# hub.net
KiCad netlist of a schematic drawn in EAGLE
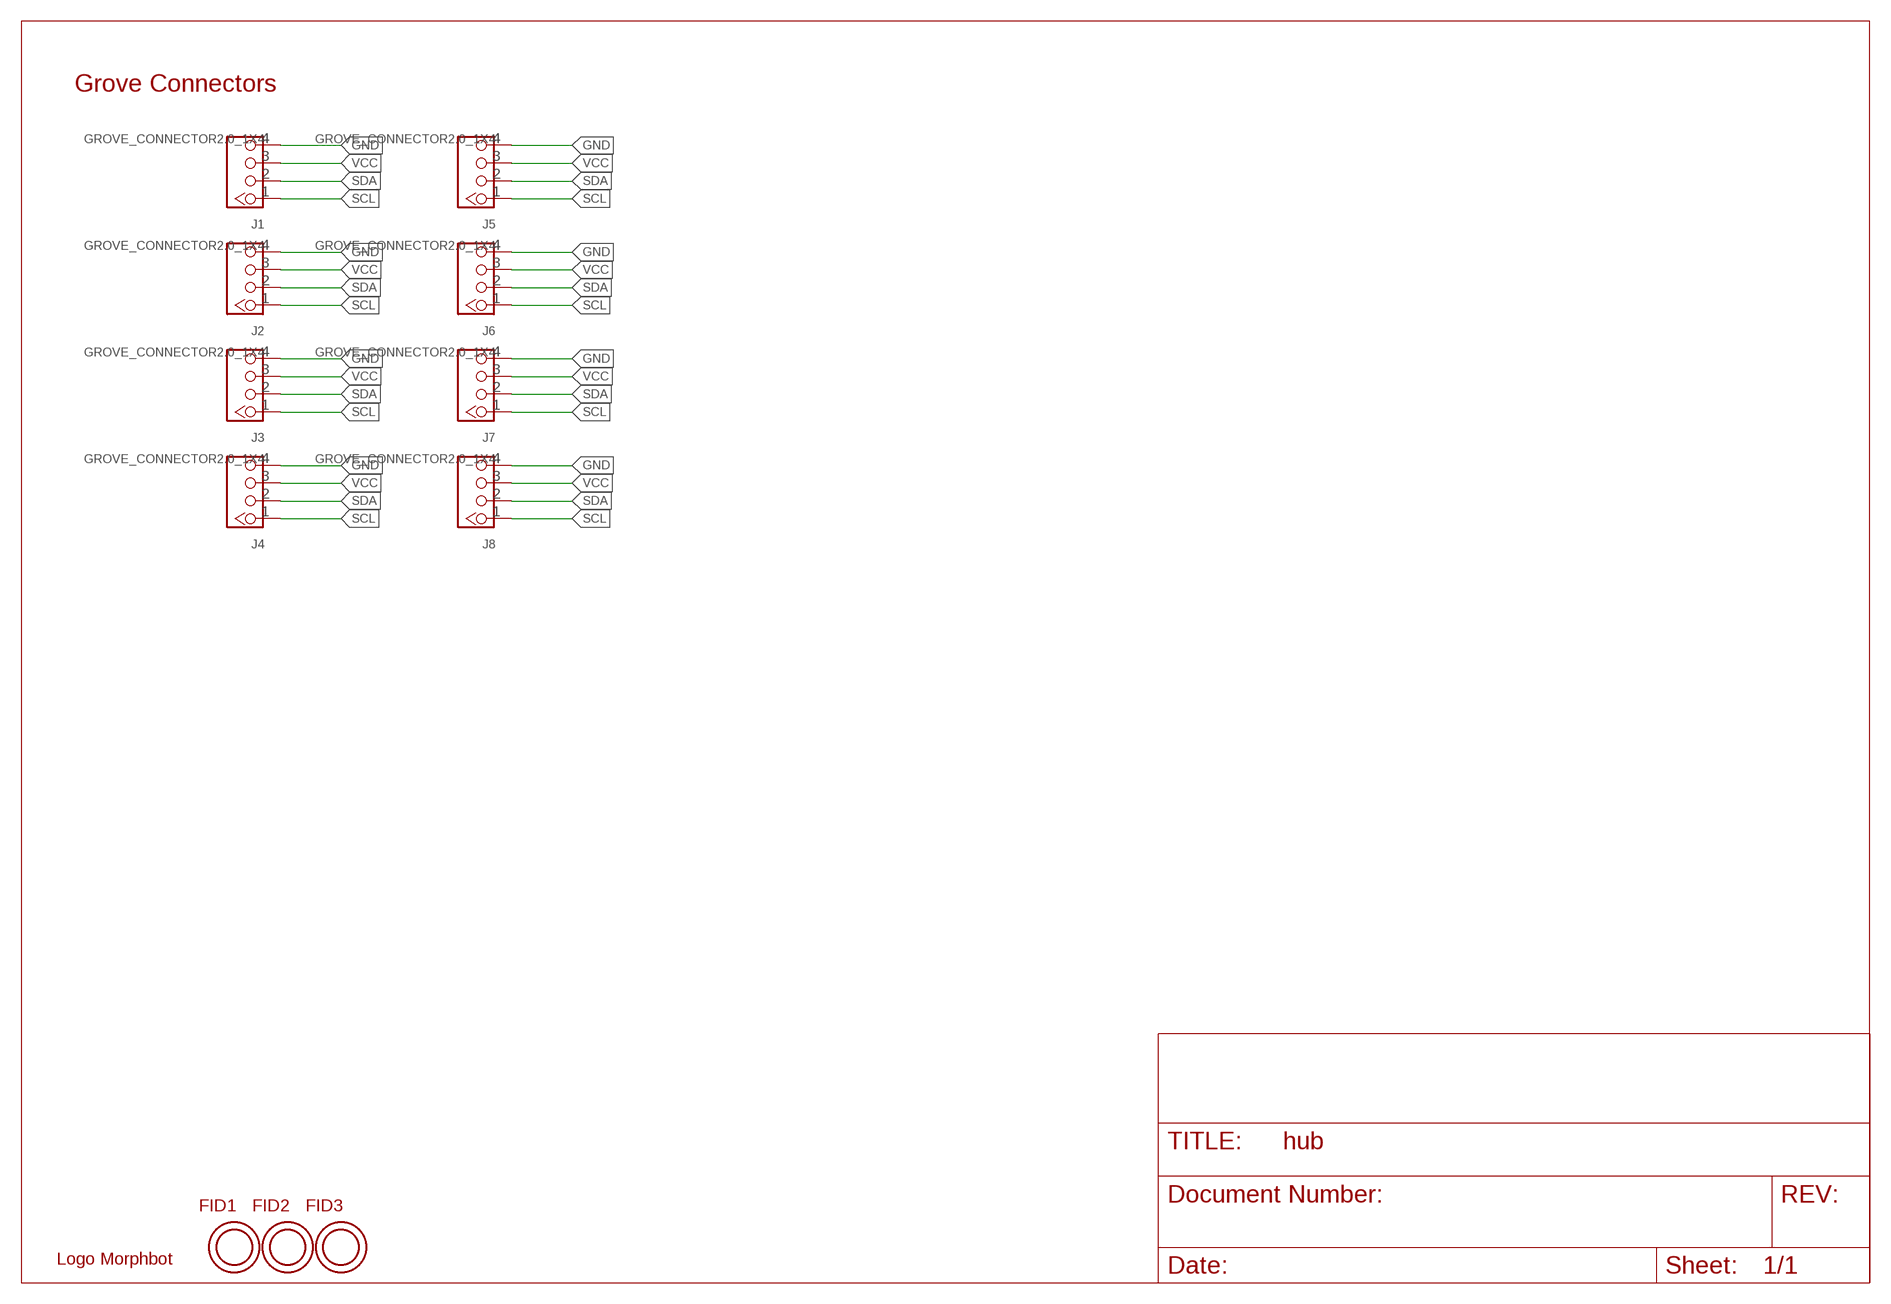
[diagram p0: schematic, sheet 1]

(export (version "E")
  (design (tool "Eeschema 10.0.6"))
  (components
    (comp (ref "FID1")
      (value "OPEN-PNP-FIDUCIAL")
      (footprint "eagle-import:OPEN-PNP-FIDUCIAL")
      (libsource (lib "eagle-import") (part "OPEN-PNP-FIDUCIAL"))
    )
    (comp (ref "FID2")
      (value "OPEN-PNP-FIDUCIAL")
      (footprint "eagle-import:OPEN-PNP-FIDUCIAL")
      (libsource (lib "eagle-import") (part "OPEN-PNP-FIDUCIAL"))
    )
    (comp (ref "FID3")
      (value "OPEN-PNP-FIDUCIAL")
      (footprint "eagle-import:OPEN-PNP-FIDUCIAL")
      (libsource (lib "eagle-import") (part "OPEN-PNP-FIDUCIAL"))
    )
    (comp (ref "J1")
      (value "GROVE_CONNECTOR2.0_1X4")
      (footprint "eagle-import:2.0_1X4_STRAIGHT")
      (libsource (lib "eagle-import") (part "GROVE_CONNECTOR2.0_1X4"))
    )
    (comp (ref "J2")
      (value "GROVE_CONNECTOR2.0_1X4")
      (footprint "eagle-import:2.0_1X4_STRAIGHT")
      (libsource (lib "eagle-import") (part "GROVE_CONNECTOR2.0_1X4"))
    )
    (comp (ref "J3")
      (value "GROVE_CONNECTOR2.0_1X4")
      (footprint "eagle-import:2.0_1X4_STRAIGHT")
      (libsource (lib "eagle-import") (part "GROVE_CONNECTOR2.0_1X4"))
    )
    (comp (ref "J4")
      (value "GROVE_CONNECTOR2.0_1X4")
      (footprint "eagle-import:2.0_1X4_STRAIGHT")
      (libsource (lib "eagle-import") (part "GROVE_CONNECTOR2.0_1X4"))
    )
    (comp (ref "J5")
      (value "GROVE_CONNECTOR2.0_1X4")
      (footprint "eagle-import:2.0_1X4_STRAIGHT")
      (libsource (lib "eagle-import") (part "GROVE_CONNECTOR2.0_1X4"))
    )
    (comp (ref "J6")
      (value "GROVE_CONNECTOR2.0_1X4")
      (footprint "eagle-import:2.0_1X4_STRAIGHT")
      (libsource (lib "eagle-import") (part "GROVE_CONNECTOR2.0_1X4"))
    )
    (comp (ref "J7")
      (value "GROVE_CONNECTOR2.0_1X4")
      (footprint "eagle-import:2.0_1X4_STRAIGHT")
      (libsource (lib "eagle-import") (part "GROVE_CONNECTOR2.0_1X4"))
    )
    (comp (ref "J8")
      (value "GROVE_CONNECTOR2.0_1X4")
      (footprint "eagle-import:2.0_1X4_STRAIGHT")
      (libsource (lib "eagle-import") (part "GROVE_CONNECTOR2.0_1X4"))
    )
    (comp (ref "U$1")
      (value "LOGO_MORPHBOT5MM")
      (footprint "eagle-import:LOGO_MORPHBOT")
      (libsource (lib "eagle-import") (part "LOGO_MORPHBOT5MM"))
    )
  )
  (nets
    (net (code "1") (name "GND") (class "Default")
      (node (ref "J1") (pin "4") (pinfunction "4_4") (pintype "bidirectional"))
      (node (ref "J2") (pin "4") (pinfunction "4_4") (pintype "bidirectional"))
      (node (ref "J3") (pin "4") (pinfunction "4_4") (pintype "bidirectional"))
      (node (ref "J4") (pin "4") (pinfunction "4_4") (pintype "bidirectional"))
      (node (ref "J5") (pin "4") (pinfunction "4_4") (pintype "bidirectional"))
      (node (ref "J6") (pin "4") (pinfunction "4_4") (pintype "bidirectional"))
      (node (ref "J7") (pin "4") (pinfunction "4_4") (pintype "bidirectional"))
      (node (ref "J8") (pin "4") (pinfunction "4_4") (pintype "bidirectional"))
    )
    (net (code "2") (name "SCL") (class "Default")
      (node (ref "J1") (pin "1") (pinfunction "1_1") (pintype "bidirectional"))
      (node (ref "J2") (pin "1") (pinfunction "1_1") (pintype "bidirectional"))
      (node (ref "J3") (pin "1") (pinfunction "1_1") (pintype "bidirectional"))
      (node (ref "J4") (pin "1") (pinfunction "1_1") (pintype "bidirectional"))
      (node (ref "J5") (pin "1") (pinfunction "1_1") (pintype "bidirectional"))
      (node (ref "J6") (pin "1") (pinfunction "1_1") (pintype "bidirectional"))
      (node (ref "J7") (pin "1") (pinfunction "1_1") (pintype "bidirectional"))
      (node (ref "J8") (pin "1") (pinfunction "1_1") (pintype "bidirectional"))
    )
    (net (code "3") (name "SDA") (class "Default")
      (node (ref "J1") (pin "2") (pinfunction "2_2") (pintype "bidirectional"))
      (node (ref "J2") (pin "2") (pinfunction "2_2") (pintype "bidirectional"))
      (node (ref "J3") (pin "2") (pinfunction "2_2") (pintype "bidirectional"))
      (node (ref "J4") (pin "2") (pinfunction "2_2") (pintype "bidirectional"))
      (node (ref "J5") (pin "2") (pinfunction "2_2") (pintype "bidirectional"))
      (node (ref "J6") (pin "2") (pinfunction "2_2") (pintype "bidirectional"))
      (node (ref "J7") (pin "2") (pinfunction "2_2") (pintype "bidirectional"))
      (node (ref "J8") (pin "2") (pinfunction "2_2") (pintype "bidirectional"))
    )
    (net (code "4") (name "VCC") (class "Default")
      (node (ref "J1") (pin "3") (pinfunction "3_3") (pintype "bidirectional"))
      (node (ref "J2") (pin "3") (pinfunction "3_3") (pintype "bidirectional"))
      (node (ref "J3") (pin "3") (pinfunction "3_3") (pintype "bidirectional"))
      (node (ref "J4") (pin "3") (pinfunction "3_3") (pintype "bidirectional"))
      (node (ref "J5") (pin "3") (pinfunction "3_3") (pintype "bidirectional"))
      (node (ref "J6") (pin "3") (pinfunction "3_3") (pintype "bidirectional"))
      (node (ref "J7") (pin "3") (pinfunction "3_3") (pintype "bidirectional"))
      (node (ref "J8") (pin "3") (pinfunction "3_3") (pintype "bidirectional"))
    )
  )
)
